# JTAG.net
KiCad netlist of a schematic drawn in Altium Designer
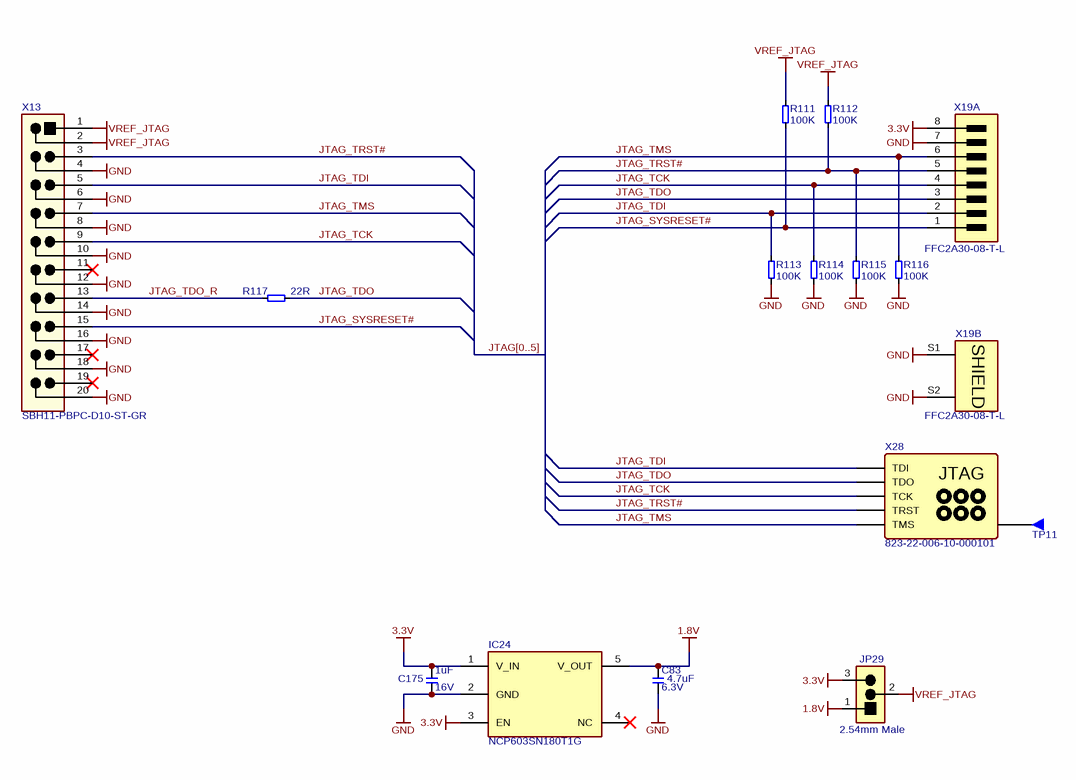
[diagram p0: JTAG.SchDoc]

(export (version "E")
  (design (tool "Eeschema 10.0.6"))
  (components
    (comp (ref "C83")
      (value "4.7uF")
      (footprint "T_CAPC0603X33N")
      (description "Capacitor Ceramic X5R 4.7uF 6.3V 20% 0603")
      (fields (field (name "TOLERANCE") "20%") (field (name "RATING") "6.3V"))
      (libsource (lib "Evaluation Board") (part "C-X5R-4.7uF-6.3V-20%-0603"))
    )
    (comp (ref "C175")
      (value "1uF")
      (footprint "T_CAPC0603X33N")
      (description "Capacitor Ceramic X5R 1uF 16V 20% 0603")
      (fields (field (name "TOLERANCE") "20%") (field (name "RATING") "16V"))
      (libsource (lib "Evaluation Board") (part "C-X5R-1uF-16V-20%-0603"))
    )
    (comp (ref "IC24")
      (value "NCP603SN180T1G")
      (footprint "T_ON_NCP603SN180T1G")
      (description "CMOS LDO Regulator")
      (fields (field (name "MANUFACTURER PART NO.") "NCP603SN180T1G"))
      (libsource (lib "Evaluation Board") (part "IC-ON-NCP603SN180T1G"))
    )
    (comp (ref "JP29")
      (value "826936-3")
      (footprint "T_TYCO_826936-3")
      (description "Jumper, 3-Pin")
      (libsource (lib "Evaluation Board") (part "CON-Tyco-826936-3-1X3-2.54mm-JP_1"))
    )
    (comp (ref "R111")
      (value "100K")
      (footprint "T_RESC0603X30N")
      (description "Resistor 100 Kohm 63mW 5% 0603")
      (fields (field (name "TOLERANCE") "5%"))
      (libsource (lib "Evaluation Board") (part "R-100KR-63mW-5%-0603"))
    )
    (comp (ref "R112")
      (value "100K")
      (footprint "T_RESC0603X30N")
      (description "Resistor 100 Kohm 63mW 5% 0603")
      (fields (field (name "TOLERANCE") "5%"))
      (libsource (lib "Evaluation Board") (part "R-100KR-63mW-5%-0603"))
    )
    (comp (ref "R113")
      (value "100K")
      (footprint "T_RESC0603X30N")
      (description "Resistor 100 Kohm 63mW 5% 0603")
      (fields (field (name "TOLERANCE") "5%"))
      (libsource (lib "Evaluation Board") (part "R-100KR-63mW-5%-0603"))
    )
    (comp (ref "R114")
      (value "100K")
      (footprint "T_RESC0603X30N")
      (description "Resistor 100 Kohm 63mW 5% 0603")
      (fields (field (name "TOLERANCE") "5%"))
      (libsource (lib "Evaluation Board") (part "R-100KR-63mW-5%-0603"))
    )
    (comp (ref "R115")
      (value "100K")
      (footprint "T_RESC0603X30N")
      (description "Resistor 100 Kohm 63mW 5% 0603")
      (fields (field (name "TOLERANCE") "5%"))
      (libsource (lib "Evaluation Board") (part "R-100KR-63mW-5%-0603"))
    )
    (comp (ref "R116")
      (value "100K")
      (footprint "T_RESC0603X30N")
      (description "Resistor 100 Kohm 63mW 5% 0603")
      (fields (field (name "TOLERANCE") "5%"))
      (libsource (lib "Evaluation Board") (part "R-100KR-63mW-5%-0603"))
    )
    (comp (ref "R117")
      (value "22R")
      (footprint "T_RESC0603X30N")
      (description "Resistor 22 ohm 63mW 5% 0603")
      (fields (field (name "TOLERANCE") "5%"))
      (libsource (lib "Evaluation Board") (part "R-22R-63mW-5%-0603"))
    )
    (comp (ref "TP11")
      (value "Testpin")
      (footprint "T_TP-THT")
      (description "Testpin TH")
      (libsource (lib "Evaluation Board") (part "Testpin"))
    )
    (comp (ref "X13")
      (value "SBH11-PBPC-D10-ST-GR")
      (footprint "T_Sullins_SBH11-PBPC-D10-ST-GR")
      (description "Header shrouded male, 2x10 pin 2.54mm pitch")
      (fields (field (name "MANUFACTURER PART NO.") "SBH11-PBPC-D10-ST-GR"))
      (libsource (lib "Evaluation Board") (part "CON-Sullins-SBH11-PBPC-D10-ST-GR"))
    )
    (comp (ref "X19")
      (value "FFC2A30-08-T-L")
      (footprint "T_GCT_FFC2A30-08-T-L")
      (description "0.50mm Pitch FFC/FPC JTAG Connector Vertical")
      (fields (field (name "MANUFACTURER PART NO.") "FFC2A30-08-T-L"))
      (libsource (lib "") (part "CON-GCT-FFC2A30-08-T-L-0.5mm_1"))
    )
    (comp (ref "X28")
      (value "CON-MM-823-22-006-10-000101")
      (footprint "T_MILL-MAX_823-22-006-10-000101")
      (description "JTAG Pogo pins")
      (fields (field (name "MANUFACTURER PART NO.") "823-22-006-10-000101"))
      (libsource (lib "Evaluation Board") (part "CON-MM-823-22-006-10-000101"))
    )
  )
  (nets
    (net (code "8") (name "/JTAG_SYSRESET#") (class "Default")
      (node (ref "R111") (pin "1") (pinfunction "1_1") (pintype "passive"))
      (node (ref "X13") (pin "15") (pinfunction "15_15") (pintype "passive"))
      (node (ref "X19") (pin "1") (pintype "passive"))
    )
    (net (code "9") (name "/JTAG_TCK") (class "Default")
      (node (ref "R114") (pin "2") (pinfunction "2_2") (pintype "passive"))
      (node (ref "X13") (pin "9") (pinfunction "9_9") (pintype "passive"))
      (node (ref "X19") (pin "4") (pintype "passive"))
      (node (ref "X28") (pin "3") (pinfunction "TCK_3") (pintype "passive"))
    )
    (net (code "10") (name "/JTAG_TDI") (class "Default")
      (node (ref "R113") (pin "2") (pinfunction "2_2") (pintype "passive"))
      (node (ref "X13") (pin "5") (pinfunction "5_5") (pintype "passive"))
      (node (ref "X19") (pin "2") (pintype "passive"))
      (node (ref "X28") (pin "1") (pinfunction "TDI_1") (pintype "passive"))
    )
    (net (code "11") (name "/JTAG_TDO") (class "Default")
      (node (ref "R117") (pin "2") (pinfunction "2_2") (pintype "passive"))
      (node (ref "X19") (pin "3") (pintype "passive"))
      (node (ref "X28") (pin "2") (pinfunction "TDO_2") (pintype "passive"))
    )
    (net (code "12") (name "/JTAG_TDO_R") (class "Default")
      (node (ref "R117") (pin "1") (pinfunction "1_1") (pintype "passive"))
      (node (ref "X13") (pin "13") (pinfunction "13_13") (pintype "passive"))
    )
    (net (code "13") (name "/JTAG_TMS") (class "Default")
      (node (ref "R116") (pin "2") (pinfunction "2_2") (pintype "passive"))
      (node (ref "X13") (pin "7") (pinfunction "7_7") (pintype "passive"))
      (node (ref "X19") (pin "6") (pintype "passive"))
      (node (ref "X28") (pin "5") (pinfunction "TMS_5") (pintype "passive"))
    )
    (net (code "14") (name "/JTAG_TRST#") (class "Default")
      (node (ref "R112") (pin "1") (pinfunction "1_1") (pintype "passive"))
      (node (ref "R115") (pin "2") (pinfunction "2_2") (pintype "passive"))
      (node (ref "X13") (pin "3") (pinfunction "3_3") (pintype "passive"))
      (node (ref "X19") (pin "5") (pintype "passive"))
      (node (ref "X28") (pin "4") (pinfunction "TRST_4") (pintype "passive"))
    )
    (net (code "15") (name "1.8V") (class "Default")
      (node (ref "C83") (pin "2") (pinfunction "2_2") (pintype "passive"))
      (node (ref "IC24") (pin "5") (pinfunction "V_OUT_5") (pintype "passive"))
      (node (ref "JP29") (pin "1") (pinfunction "1_1") (pintype "passive"))
    )
    (net (code "16") (name "3.3V") (class "Default")
      (node (ref "C175") (pin "2") (pinfunction "2_2") (pintype "passive"))
      (node (ref "IC24") (pin "1") (pinfunction "V_IN_1") (pintype "power_in"))
      (node (ref "IC24") (pin "3") (pinfunction "EN_3") (pintype "passive"))
      (node (ref "JP29") (pin "3") (pinfunction "3_3") (pintype "passive"))
      (node (ref "X19") (pin "8") (pintype "passive"))
    )
    (net (code "17") (name "GND") (class "Default")
      (node (ref "C175") (pin "1") (pinfunction "1_1") (pintype "passive"))
      (node (ref "C83") (pin "1") (pinfunction "1_1") (pintype "passive"))
      (node (ref "IC24") (pin "2") (pinfunction "GND_2") (pintype "power_in"))
      (node (ref "R113") (pin "1") (pinfunction "1_1") (pintype "passive"))
      (node (ref "R114") (pin "1") (pinfunction "1_1") (pintype "passive"))
      (node (ref "R115") (pin "1") (pinfunction "1_1") (pintype "passive"))
      (node (ref "R116") (pin "1") (pinfunction "1_1") (pintype "passive"))
      (node (ref "X13") (pin "10") (pinfunction "10_10") (pintype "passive"))
      (node (ref "X13") (pin "12") (pinfunction "12_12") (pintype "passive"))
      (node (ref "X13") (pin "14") (pinfunction "14_14") (pintype "passive"))
      (node (ref "X13") (pin "16") (pinfunction "16_16") (pintype "passive"))
      (node (ref "X13") (pin "18") (pinfunction "18_18") (pintype "passive"))
      (node (ref "X13") (pin "20") (pinfunction "20_20") (pintype "passive"))
      (node (ref "X13") (pin "4") (pinfunction "4_4") (pintype "passive"))
      (node (ref "X13") (pin "6") (pinfunction "6_6") (pintype "passive"))
      (node (ref "X13") (pin "8") (pinfunction "8_8") (pintype "passive"))
      (node (ref "X19") (pin "7") (pintype "passive"))
      (node (ref "X19") (pin "S1") (pinfunction "SHIELD_S1") (pintype "passive"))
      (node (ref "X19") (pin "S2") (pinfunction "SHIELD_S2") (pintype "passive"))
    )
    (net (code "18") (name "Net-(TP11-Pad1)") (class "Default")
      (node (ref "TP11") (pin "1") (pinfunction "1_1") (pintype "passive"))
      (node (ref "X28") (pin "6") (pintype "passive"))
    )
    (net (code "19") (name "VREF_JTAG") (class "Default")
      (node (ref "JP29") (pin "2") (pinfunction "2_2") (pintype "passive"))
      (node (ref "R111") (pin "2") (pinfunction "2_2") (pintype "passive"))
      (node (ref "R112") (pin "2") (pinfunction "2_2") (pintype "passive"))
      (node (ref "X13") (pin "1") (pinfunction "1_1") (pintype "passive"))
      (node (ref "X13") (pin "2") (pinfunction "2_2") (pintype "passive"))
    )
    (net (code "20") (name "unconnected-(IC24-NC-Pad4)") (class "Default")
      (node (ref "IC24") (pin "4") (pinfunction "NC_4") (pintype "passive+no_connect"))
    )
    (net (code "21") (name "unconnected-(X13-Pad11)") (class "Default")
      (node (ref "X13") (pin "11") (pinfunction "11_11") (pintype "passive+no_connect"))
    )
    (net (code "22") (name "unconnected-(X13-Pad17)") (class "Default")
      (node (ref "X13") (pin "17") (pinfunction "17_17") (pintype "passive+no_connect"))
    )
    (net (code "23") (name "unconnected-(X13-Pad19)") (class "Default")
      (node (ref "X13") (pin "19") (pinfunction "19_19") (pintype "passive+no_connect"))
    )
  )
)
